# voltage.net
KiCad netlist of a schematic drawn in EAGLE
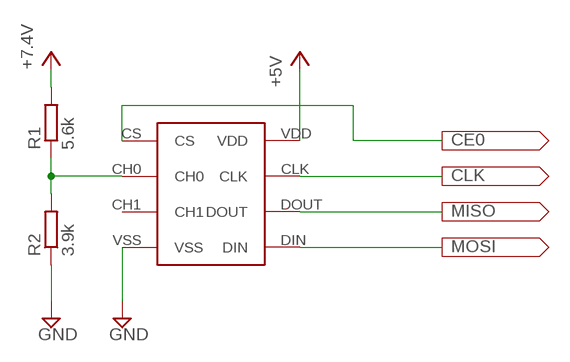
[diagram p0: schematic, sheet 1]

(export (version "E")
  (design (tool "Eeschema 10.0.6"))
  (components
    (comp (ref "R1")
      (value "5.6k")
      (footprint "eagle-import:0204_7")
      (libsource (lib "eagle-import") (part "R-EU_0204/7"))
    )
    (comp (ref "R2")
      (value "3.9k")
      (footprint "eagle-import:0204_7")
      (libsource (lib "eagle-import") (part "R-EU_0204/7"))
    )
    (comp (ref "U$1")
      (value "MCP3002")
      (footprint "eagle-import:MCP3002")
      (libsource (lib "eagle-import") (part "MCP3002"))
    )
  )
  (nets
    (net (code "1") (name "+5V") (class "Default")
      (node (ref "U$1") (pin "VDD") (pinfunction "VDD_VDD") (pintype "bidirectional"))
    )
    (net (code "2") (name "+7.4V") (class "Default")
      (node (ref "R1") (pin "2") (pinfunction "2_2") (pintype "passive"))
    )
    (net (code "3") (name "GND") (class "Default")
      (node (ref "R2") (pin "1") (pinfunction "1_1") (pintype "passive"))
      (node (ref "U$1") (pin "VSS") (pinfunction "VSS_VSS") (pintype "bidirectional"))
    )
    (net (code "4") (name "Net-(R1-Pad1)") (class "Default")
      (node (ref "R1") (pin "1") (pinfunction "1_1") (pintype "passive"))
      (node (ref "R2") (pin "2") (pinfunction "2_2") (pintype "passive"))
      (node (ref "U$1") (pin "CH0") (pinfunction "CH0_CH0") (pintype "bidirectional"))
    )
    (net (code "5") (name "unconnected-(U$1-PadCH1)") (class "Default")
      (node (ref "U$1") (pin "CH1") (pinfunction "CH1_CH1") (pintype "bidirectional"))
    )
    (net (code "6") (name "unconnected-(U$1-PadCLK)") (class "Default")
      (node (ref "U$1") (pin "CLK") (pinfunction "CLK_CLK") (pintype "bidirectional"))
    )
    (net (code "7") (name "unconnected-(U$1-PadCS)") (class "Default")
      (node (ref "U$1") (pin "CS") (pinfunction "CS_CS") (pintype "bidirectional"))
    )
    (net (code "8") (name "unconnected-(U$1-PadDIN)") (class "Default")
      (node (ref "U$1") (pin "DIN") (pinfunction "DIN_DIN") (pintype "bidirectional"))
    )
    (net (code "9") (name "unconnected-(U$1-PadDOUT)") (class "Default")
      (node (ref "U$1") (pin "DOUT") (pinfunction "DOUT_DOUT") (pintype "bidirectional"))
    )
  )
)
